# 2025_11_15_drone.net
KiCad netlist of a schematic drawn in EasyEDA Pro
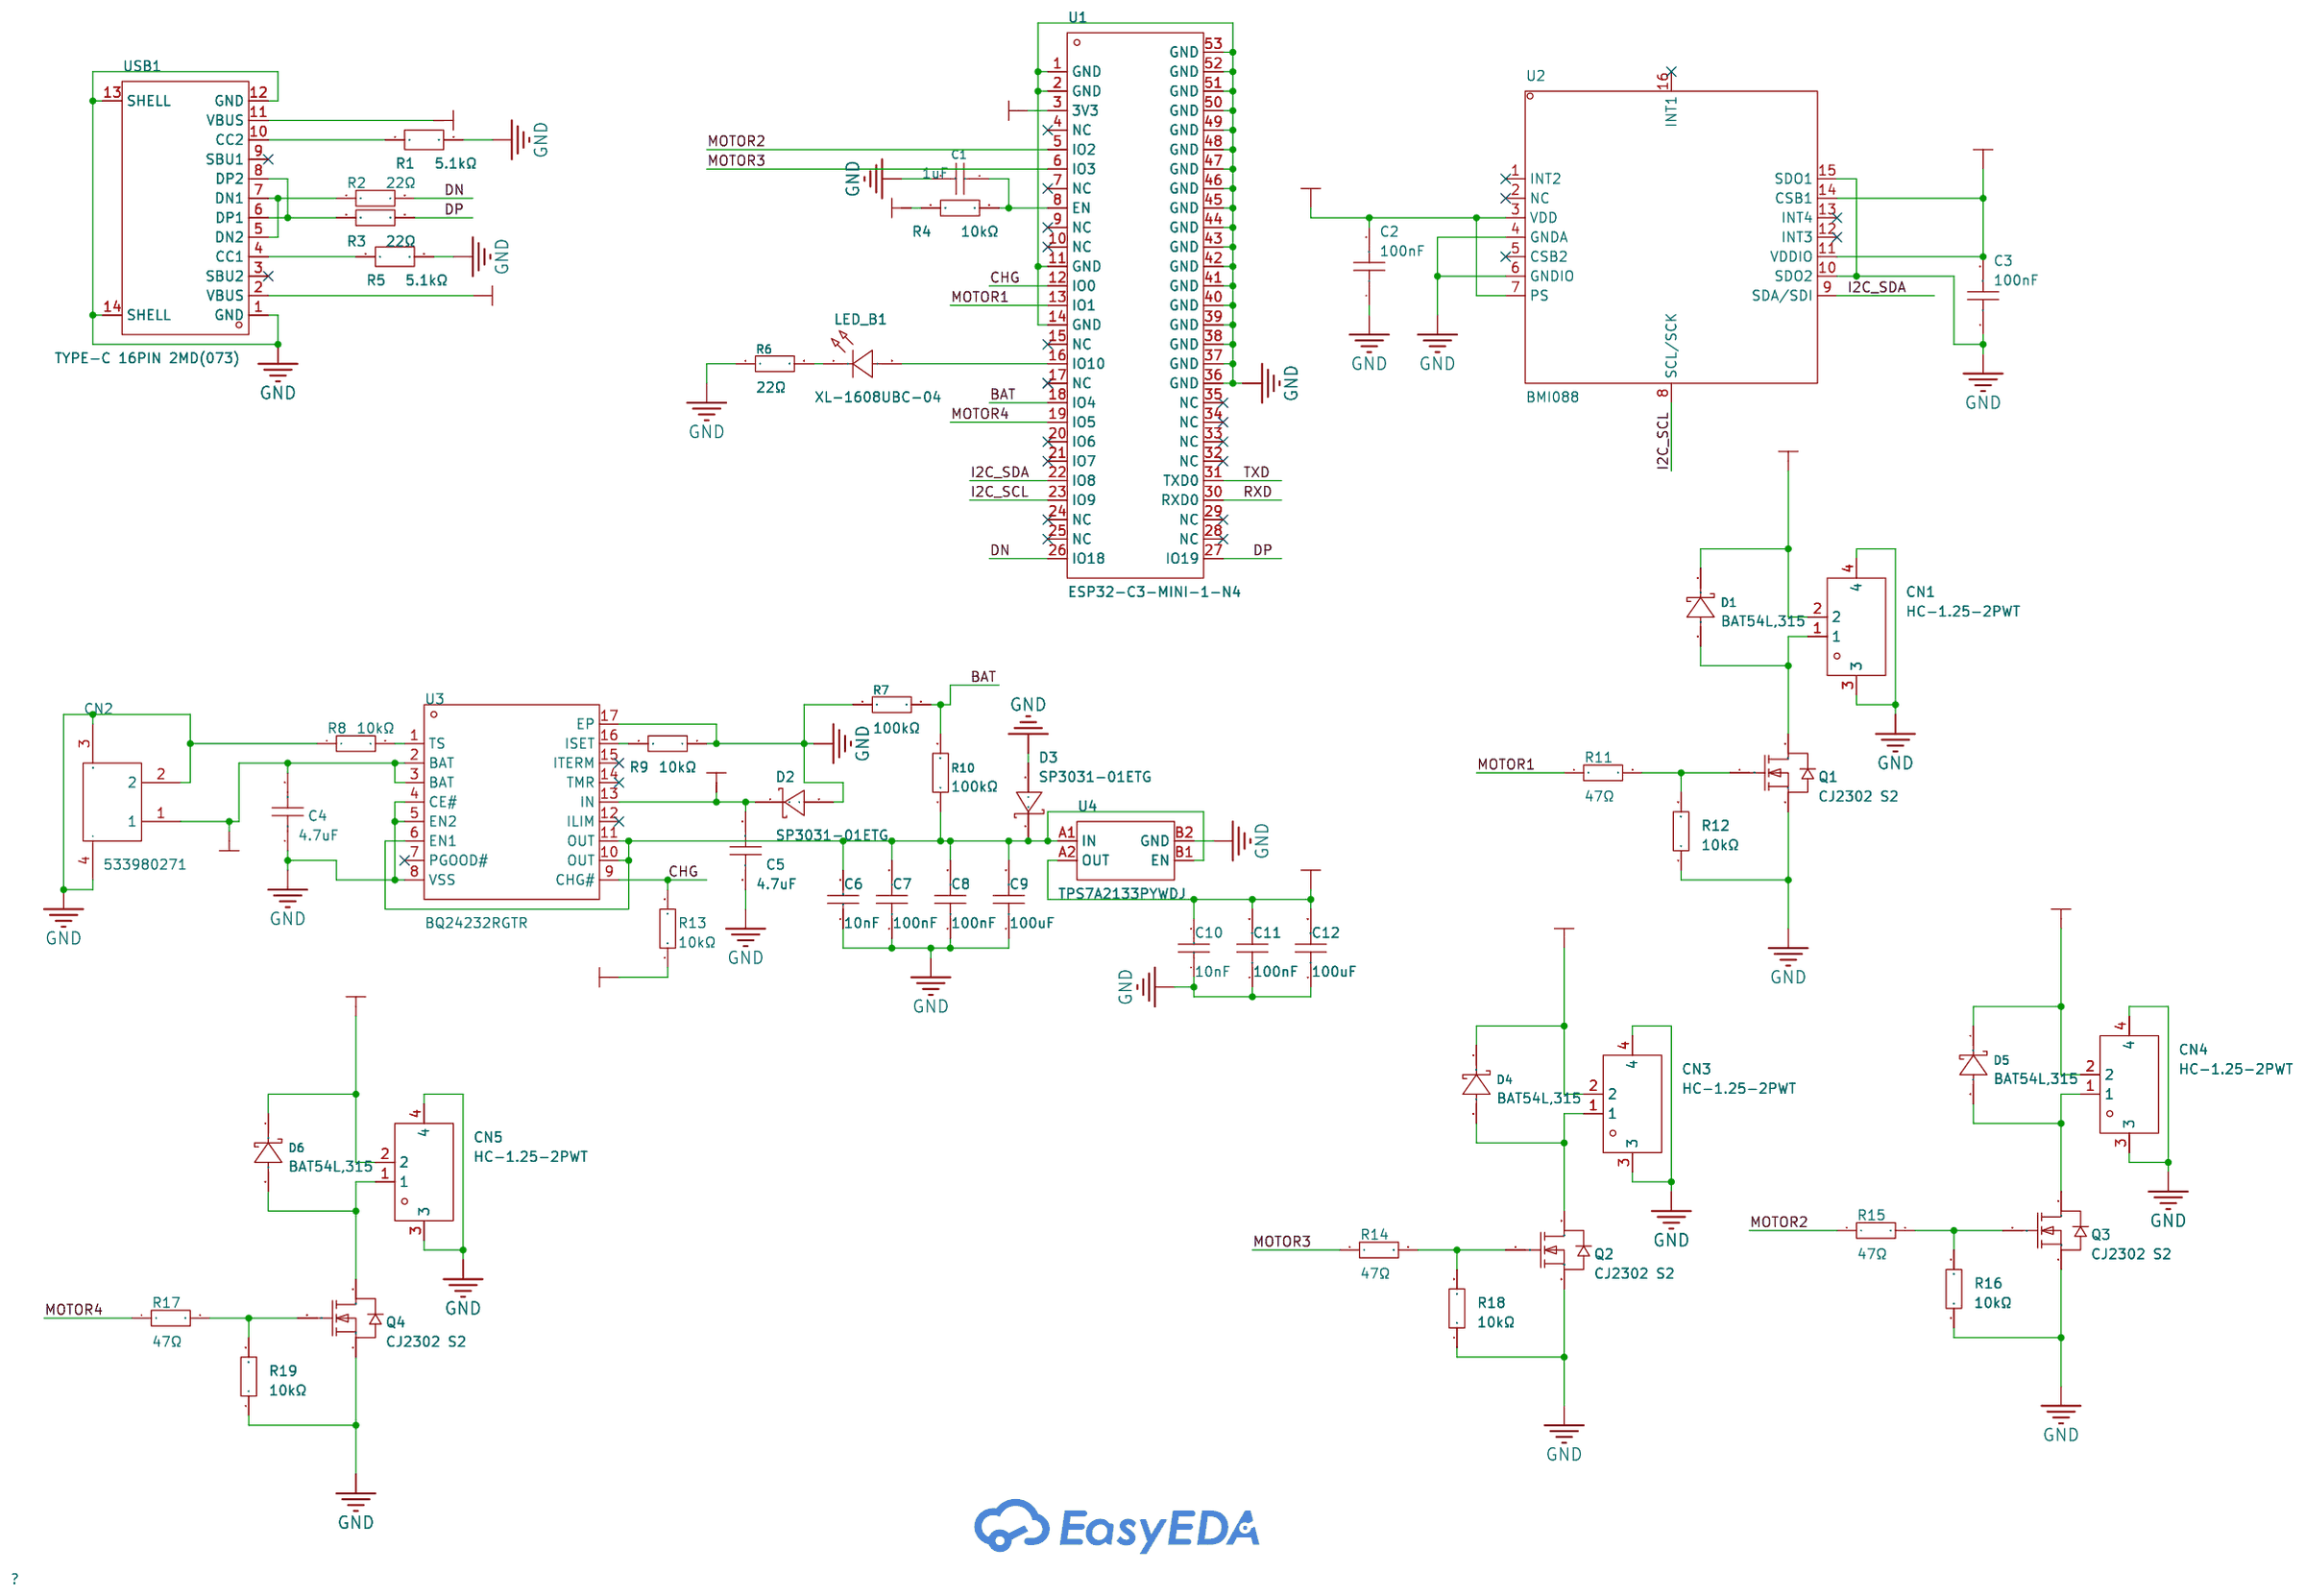
[diagram p0: schematic sheet]

(export (version "E")
  (design (tool "Eeschema 10.0.6"))
  (components
    (comp (ref "C1")
      (value "1uF")
      (footprint "easyedapro:C0402")
      (description "Capacitance:1uF Tolerance:±10% Tolerance:±10% Voltage Rating:16V Temperature Coefficient:X5R")
      (fields
        (field (name "Manufacturer Part") "CL05A105KO5NNNC")
        (field (name "Manufacturer") "SAMSUNG(三星)")
      )
      (libsource (lib "easyedapro") (part "CL05A105KO5NNNC"))
    )
    (comp (ref "C2")
      (value "100nF")
      (footprint "easyedapro:C0402")
      (fields
        (field (name "Manufacturer Part") "CL05B104KO5NNNC")
        (field (name "Manufacturer") "SAMSUNG(三星)")
      )
      (libsource (lib "easyedapro") (part "CL05B104KO5NNNC"))
    )
    (comp (ref "C3")
      (value "100nF")
      (footprint "easyedapro:C0402")
      (fields
        (field (name "Manufacturer Part") "CL05B104KO5NNNC")
        (field (name "Manufacturer") "SAMSUNG(三星)")
      )
      (libsource (lib "easyedapro") (part "CL05B104KO5NNNC"))
    )
    (comp (ref "C4")
      (value "4.7uF")
      (footprint "easyedapro:C0402")
      (description "Capacitance:4.7uF Tolerance:±20% Tolerance:±20% Voltage Rating:6.3V Temperature Coefficient:X5R")
      (fields
        (field (name "Manufacturer Part") "CL05A475MQ5NRNC")
        (field (name "Manufacturer") "SAMSUNG(三星)")
      )
      (libsource (lib "easyedapro") (part "CL05A475MQ5NRNC_C307423"))
    )
    (comp (ref "C5")
      (value "4.7uF")
      (footprint "easyedapro:C0402")
      (description "Capacitance:4.7uF Tolerance:±20% Tolerance:±20% Voltage Rating:6.3V Temperature Coefficient:X5R")
      (fields
        (field (name "Manufacturer Part") "CL05A475MQ5NRNC")
        (field (name "Manufacturer") "SAMSUNG(三星)")
      )
      (libsource (lib "easyedapro") (part "CL05A475MQ5NRNC_C307423"))
    )
    (comp (ref "C6")
      (value "10nF")
      (footprint "easyedapro:C0402")
      (description "Capacitance:10nF Tolerance:±10% Tolerance:±10% Voltage Rating:50V Temperature Coefficient:X7R")
      (fields
        (field (name "Manufacturer Part") "CL05B103KB5NNNC")
        (field (name "Manufacturer") "SAMSUNG(三星)")
      )
      (libsource (lib "easyedapro") (part "CL05B103KB5NNNC"))
    )
    (comp (ref "C7")
      (value "100nF")
      (footprint "easyedapro:C0603")
      (description "Capacitance:100nF Tolerance:±10% Tolerance:±10% Voltage Rating:50V Temperature Coefficient:X7R")
      (fields
        (field (name "Manufacturer Part") "CC0603KRX7R9BB104")
        (field (name "Manufacturer") "YAGEO(国巨)")
      )
      (libsource (lib "easyedapro") (part "CC0603KRX7R9BB104"))
    )
    (comp (ref "C8")
      (value "100nF")
      (footprint "easyedapro:C0603")
      (description "Capacitance:100nF Tolerance:±10% Tolerance:±10% Voltage Rating:50V Temperature Coefficient:X7R")
      (fields
        (field (name "Manufacturer Part") "CC0603KRX7R9BB104")
        (field (name "Manufacturer") "YAGEO(国巨)")
      )
      (libsource (lib "easyedapro") (part "CC0603KRX7R9BB104"))
    )
    (comp (ref "C9")
      (value "100uF")
      (footprint "easyedapro:C1206")
      (description "Capacitance:100uF Tolerance:±20% Tolerance:±20% Voltage Rating:10V Temperature Coefficient:X5R")
      (fields
        (field (name "Manufacturer Part") "HGC1206R5107M100NSPJ")
        (field (name "Manufacturer") "Chinocera(华瓷)")
      )
      (libsource (lib "easyedapro") (part "HGC1206R5107M100NSPJ"))
    )
    (comp (ref "C10")
      (value "10nF")
      (footprint "easyedapro:C0402")
      (description "Capacitance:10nF Tolerance:±10% Tolerance:±10% Voltage Rating:50V Temperature Coefficient:X7R")
      (fields
        (field (name "Manufacturer Part") "CL05B103KB5NNNC")
        (field (name "Manufacturer") "SAMSUNG(三星)")
      )
      (libsource (lib "easyedapro") (part "CL05B103KB5NNNC"))
    )
    (comp (ref "C11")
      (value "100nF")
      (footprint "easyedapro:C0603")
      (description "Capacitance:100nF Tolerance:±10% Tolerance:±10% Voltage Rating:50V Temperature Coefficient:X7R")
      (fields
        (field (name "Manufacturer Part") "CC0603KRX7R9BB104")
        (field (name "Manufacturer") "YAGEO(国巨)")
      )
      (libsource (lib "easyedapro") (part "CC0603KRX7R9BB104"))
    )
    (comp (ref "C12")
      (value "100uF")
      (footprint "easyedapro:C1206")
      (description "Capacitance:100uF Tolerance:±20% Tolerance:±20% Voltage Rating:10V Temperature Coefficient:X5R")
      (fields
        (field (name "Manufacturer Part") "HGC1206R5107M100NSPJ")
        (field (name "Manufacturer") "Chinocera(华瓷)")
      )
      (libsource (lib "easyedapro") (part "HGC1206R5107M100NSPJ"))
    )
    (comp (ref "CN1")
      (value "HC-1.25-2PWT")
      (footprint "easyedapro:CONN-SMD_2P-P1.25-HC-1.25-2PWT")
      (fields (field (name "Manufacturer") "HCTL(华灿天禄)"))
      (libsource (lib "easyedapro") (part "HC-1.25-2PWT"))
    )
    (comp (ref "CN2")
      (value "533980271")
      (footprint "easyedapro:CONN-SMD_2P-P1.25_053398-0X71")
      (fields (field (name "Manufacturer") "MOLEX"))
      (libsource (lib "easyedapro") (part "0533980271"))
    )
    (comp (ref "CN3")
      (value "HC-1.25-2PWT")
      (footprint "easyedapro:CONN-SMD_2P-P1.25-HC-1.25-2PWT")
      (fields (field (name "Manufacturer") "HCTL(华灿天禄)"))
      (libsource (lib "easyedapro") (part "HC-1.25-2PWT"))
    )
    (comp (ref "CN4")
      (value "HC-1.25-2PWT")
      (footprint "easyedapro:CONN-SMD_2P-P1.25-HC-1.25-2PWT")
      (fields (field (name "Manufacturer") "HCTL(华灿天禄)"))
      (libsource (lib "easyedapro") (part "HC-1.25-2PWT"))
    )
    (comp (ref "CN5")
      (value "HC-1.25-2PWT")
      (footprint "easyedapro:CONN-SMD_2P-P1.25-HC-1.25-2PWT")
      (fields (field (name "Manufacturer") "HCTL(华灿天禄)"))
      (libsource (lib "easyedapro") (part "HC-1.25-2PWT"))
    )
    (comp (ref "D1")
      (value "BAT54L,315")
      (footprint "easyedapro:DFN1006-2L-RD")
      (fields (field (name "Manufacturer") "Nexperia(安世)"))
      (libsource (lib "easyedapro") (part "BAT54L,315"))
    )
    (comp (ref "D2")
      (value "SP3031-01ETG")
      (footprint "easyedapro:SOD-882_L1.0-W0.6-RD")
      (fields (field (name "Manufacturer") "Littelfuse(美国力特)"))
      (libsource (lib "easyedapro") (part "SP3031-01ETG"))
    )
    (comp (ref "D3")
      (value "SP3031-01ETG")
      (footprint "easyedapro:SOD-882_L1.0-W0.6-RD")
      (fields (field (name "Manufacturer") "Littelfuse(美国力特)"))
      (libsource (lib "easyedapro") (part "SP3031-01ETG"))
    )
    (comp (ref "D4")
      (value "BAT54L,315")
      (footprint "easyedapro:DFN1006-2L-RD")
      (fields (field (name "Manufacturer") "Nexperia(安世)"))
      (libsource (lib "easyedapro") (part "BAT54L,315"))
    )
    (comp (ref "D5")
      (value "BAT54L,315")
      (footprint "easyedapro:DFN1006-2L-RD")
      (fields (field (name "Manufacturer") "Nexperia(安世)"))
      (libsource (lib "easyedapro") (part "BAT54L,315"))
    )
    (comp (ref "D6")
      (value "BAT54L,315")
      (footprint "easyedapro:DFN1006-2L-RD")
      (fields (field (name "Manufacturer") "Nexperia(安世)"))
      (libsource (lib "easyedapro") (part "BAT54L,315"))
    )
    (comp (ref "LED_B1")
      (value "XL-1608UBC-04")
      (footprint "easyedapro:LED0603-RD_BLUE")
      (fields (field (name "Manufacturer") "XINGLIGHT(成兴光)"))
      (libsource (lib "easyedapro") (part "XL-1608UBC-04"))
    )
    (comp (ref "Q1")
      (value "CJ2302 S2")
      (footprint "easyedapro:SOT-23-3_L3.0-W1.7-P0.95-LS2.9-BR")
      (fields (field (name "Manufacturer") "CJ(江苏长电/长晶)"))
      (libsource (lib "easyedapro") (part "CJ2302 S2"))
    )
    (comp (ref "Q2")
      (value "CJ2302 S2")
      (footprint "easyedapro:SOT-23-3_L3.0-W1.7-P0.95-LS2.9-BR")
      (fields (field (name "Manufacturer") "CJ(江苏长电/长晶)"))
      (libsource (lib "easyedapro") (part "CJ2302 S2"))
    )
    (comp (ref "Q3")
      (value "CJ2302 S2")
      (footprint "easyedapro:SOT-23-3_L3.0-W1.7-P0.95-LS2.9-BR")
      (fields (field (name "Manufacturer") "CJ(江苏长电/长晶)"))
      (libsource (lib "easyedapro") (part "CJ2302 S2"))
    )
    (comp (ref "Q4")
      (value "CJ2302 S2")
      (footprint "easyedapro:SOT-23-3_L3.0-W1.7-P0.95-LS2.9-BR")
      (fields (field (name "Manufacturer") "CJ(江苏长电/长晶)"))
      (libsource (lib "easyedapro") (part "CJ2302 S2"))
    )
    (comp (ref "R1")
      (value "5.1kΩ")
      (footprint "easyedapro:R0603")
      (fields (field (name "Manufacturer Part") "FRC0603F5101TS") (field (name "Manufacturer") "FOJAN(富捷)"))
      (libsource (lib "easyedapro") (part "FRC0603F5101TS"))
    )
    (comp (ref "R2")
      (value "22Ω")
      (footprint "easyedapro:R0603")
      (fields
        (field (name "Manufacturer Part") "0603WAF220JT5E")
        (field (name "Manufacturer") "UNI-ROYAL(厚声)")
      )
      (libsource (lib "easyedapro") (part "0603WAF220JT5E"))
    )
    (comp (ref "R3")
      (value "22Ω")
      (footprint "easyedapro:R0603")
      (fields
        (field (name "Manufacturer Part") "0603WAF220JT5E")
        (field (name "Manufacturer") "UNI-ROYAL(厚声)")
      )
      (libsource (lib "easyedapro") (part "0603WAF220JT5E"))
    )
    (comp (ref "R4")
      (value "10kΩ")
      (footprint "easyedapro:R0603")
      (fields (field (name "Manufacturer Part") "RC0603FR-0710KL") (field (name "Manufacturer") "YAGEO(国巨)"))
      (libsource (lib "easyedapro") (part "RC0603FR-0710KL"))
    )
    (comp (ref "R5")
      (value "5.1kΩ")
      (footprint "easyedapro:R0603")
      (fields (field (name "Manufacturer Part") "FRC0603F5101TS") (field (name "Manufacturer") "FOJAN(富捷)"))
      (libsource (lib "easyedapro") (part "FRC0603F5101TS"))
    )
    (comp (ref "R6")
      (value "22Ω")
      (footprint "easyedapro:R0402")
      (fields
        (field (name "Manufacturer Part") "0402WGF220JTCE")
        (field (name "Manufacturer") "UNI-ROYAL(厚声)")
      )
      (libsource (lib "easyedapro") (part "0402WGF220JTCE"))
    )
    (comp (ref "R7")
      (value "100kΩ")
      (footprint "easyedapro:R0603")
      (fields (field (name "Manufacturer Part") "RC0603FR-07100KL") (field (name "Manufacturer") "YAGEO(国巨)"))
      (libsource (lib "easyedapro") (part "RC0603FR-07100KL"))
    )
    (comp (ref "R8")
      (value "10kΩ")
      (footprint "easyedapro:R0603")
      (fields (field (name "Manufacturer Part") "RC0603FR-0710KL") (field (name "Manufacturer") "YAGEO(国巨)"))
      (libsource (lib "easyedapro") (part "RC0603FR-0710KL"))
    )
    (comp (ref "R9")
      (value "10kΩ")
      (footprint "easyedapro:R0603")
      (fields (field (name "Manufacturer Part") "RC0603FR-0710KL") (field (name "Manufacturer") "YAGEO(国巨)"))
      (libsource (lib "easyedapro") (part "RC0603FR-0710KL"))
    )
    (comp (ref "R10")
      (value "100kΩ")
      (footprint "easyedapro:R0603")
      (fields (field (name "Manufacturer Part") "RC0603FR-07100KL") (field (name "Manufacturer") "YAGEO(国巨)"))
      (libsource (lib "easyedapro") (part "RC0603FR-07100KL"))
    )
    (comp (ref "R11")
      (value "47Ω")
      (footprint "easyedapro:R0402")
      (fields (field (name "Manufacturer Part") "RC0402FR-0747RL") (field (name "Manufacturer") "YAGEO(国巨)"))
      (libsource (lib "easyedapro") (part "RC0402FR-0747RL"))
    )
    (comp (ref "R12")
      (value "10kΩ")
      (footprint "easyedapro:R0402")
      (fields (field (name "Manufacturer Part") "RC0402FR-0710KL") (field (name "Manufacturer") "YAGEO(国巨)"))
      (libsource (lib "easyedapro") (part "RC0402FR-0710KL"))
    )
    (comp (ref "R13")
      (value "10kΩ")
      (footprint "easyedapro:R0603")
      (fields (field (name "Manufacturer Part") "RC0603FR-0710KL") (field (name "Manufacturer") "YAGEO(国巨)"))
      (libsource (lib "easyedapro") (part "RC0603FR-0710KL"))
    )
    (comp (ref "R14")
      (value "47Ω")
      (footprint "easyedapro:R0402")
      (fields (field (name "Manufacturer Part") "RC0402FR-0747RL") (field (name "Manufacturer") "YAGEO(国巨)"))
      (libsource (lib "easyedapro") (part "RC0402FR-0747RL"))
    )
    (comp (ref "R15")
      (value "47Ω")
      (footprint "easyedapro:R0402")
      (fields (field (name "Manufacturer Part") "RC0402FR-0747RL") (field (name "Manufacturer") "YAGEO(国巨)"))
      (libsource (lib "easyedapro") (part "RC0402FR-0747RL"))
    )
    (comp (ref "R16")
      (value "10kΩ")
      (footprint "easyedapro:R0402")
      (fields (field (name "Manufacturer Part") "RC0402FR-0710KL") (field (name "Manufacturer") "YAGEO(国巨)"))
      (libsource (lib "easyedapro") (part "RC0402FR-0710KL"))
    )
    (comp (ref "R17")
      (value "47Ω")
      (footprint "easyedapro:R0402")
      (fields (field (name "Manufacturer Part") "RC0402FR-0747RL") (field (name "Manufacturer") "YAGEO(国巨)"))
      (libsource (lib "easyedapro") (part "RC0402FR-0747RL"))
    )
    (comp (ref "R18")
      (value "10kΩ")
      (footprint "easyedapro:R0402")
      (fields (field (name "Manufacturer Part") "RC0402FR-0710KL") (field (name "Manufacturer") "YAGEO(国巨)"))
      (libsource (lib "easyedapro") (part "RC0402FR-0710KL"))
    )
    (comp (ref "R19")
      (value "10kΩ")
      (footprint "easyedapro:R0402")
      (fields (field (name "Manufacturer Part") "RC0402FR-0710KL") (field (name "Manufacturer") "YAGEO(国巨)"))
      (libsource (lib "easyedapro") (part "RC0402FR-0710KL"))
    )
    (comp (ref "U1")
      (value "ESP32-C3-MINI-1-N4")
      (footprint "easyedapro:WIFIM-SMD_ESP32-C3-MINI-1")
      (fields (field (name "Manufacturer") "ESPRESSIF(乐鑫)"))
      (libsource (lib "easyedapro") (part "ESP32-C3-MINI-1-N4"))
    )
    (comp (ref "U2")
      (value "BMI088")
      (footprint "easyedapro:LGA-16_L4.5-W3.0-P0.50-BL")
      (description "Sensor Type:加速度计陀螺仪 Operating Temperature:-40°C~+85°C Operating Temperature:-40°C~+85°C")
      (fields (field (name "Manufacturer") "Bosch(博世)"))
      (libsource (lib "easyedapro") (part "BMI088"))
    )
    (comp (ref "U3")
      (value "BQ24232RGTR")
      (footprint "easyedapro:VQFN-16_L3.0-W3.0-P0.50-TL-EP")
      (fields (field (name "Manufacturer") "TI(德州仪器)"))
      (libsource (lib "easyedapro") (part "BQ24232RGTR"))
    )
    (comp (ref "U4")
      (value "TPS7A2133PYWDJ")
      (footprint "easyedapro:DSBGA-4_L0.6-W0.6-P0.35-TL")
      (fields (field (name "Manufacturer") "TI(德州仪器)"))
      (libsource (lib "easyedapro") (part "TPS7A2133PYWDJ"))
    )
    (comp (ref "USB1")
      (value "TYPE-C 16PIN 2MD(073)")
      (footprint "easyedapro:USB-C-SMD_TYPE-C-6PIN-2MD-073")
      (fields (field (name "Manufacturer") "SHOU HAN(首韩)"))
      (libsource (lib "easyedapro") (part "TYPE-C 16PIN 2MD(073)"))
    )
  )
  (nets
    (net (code "1") (name "/BAT") (class "Default")
      (node (ref "R10") (pin "2") (pinfunction "2_2") (pintype "input"))
      (node (ref "R7") (pin "1") (pinfunction "1_1") (pintype "input"))
      (node (ref "U1") (pin "18") (pinfunction "IO4_18") (pintype "unspecified"))
    )
    (net (code "2") (name "/CHG") (class "Default")
      (node (ref "R13") (pin "2") (pinfunction "2_2") (pintype "input"))
      (node (ref "U1") (pin "12") (pinfunction "IO0_12") (pintype "unspecified"))
      (node (ref "U3") (pin "9") (pinfunction "CHG#_9") (pintype "unspecified"))
    )
    (net (code "3") (name "/DN") (class "Default")
      (node (ref "R2") (pin "2") (pinfunction "2_2") (pintype "input"))
      (node (ref "U1") (pin "26") (pinfunction "IO18_26") (pintype "unspecified"))
    )
    (net (code "4") (name "/DP") (class "Default")
      (node (ref "R3") (pin "2") (pinfunction "2_2") (pintype "input"))
      (node (ref "U1") (pin "27") (pinfunction "IO19_27") (pintype "unspecified"))
    )
    (net (code "5") (name "/I2C_SCL") (class "Default")
      (node (ref "U1") (pin "23") (pinfunction "IO9_23") (pintype "unspecified"))
      (node (ref "U2") (pin "8") (pinfunction "SCL/SCK_8") (pintype "input"))
    )
    (net (code "6") (name "/I2C_SDA") (class "Default")
      (node (ref "U1") (pin "22") (pinfunction "IO8_22") (pintype "unspecified"))
      (node (ref "U2") (pin "9") (pinfunction "SDA/SDI_9") (pintype "input"))
    )
    (net (code "7") (name "/MOTOR1") (class "Default")
      (node (ref "R11") (pin "1") (pinfunction "1_1") (pintype "input"))
      (node (ref "U1") (pin "13") (pinfunction "IO1_13") (pintype "unspecified"))
    )
    (net (code "8") (name "/MOTOR2") (class "Default")
      (node (ref "R15") (pin "1") (pinfunction "1_1") (pintype "input"))
      (node (ref "U1") (pin "5") (pinfunction "IO2_5") (pintype "unspecified"))
    )
    (net (code "9") (name "/MOTOR3") (class "Default")
      (node (ref "R14") (pin "1") (pinfunction "1_1") (pintype "input"))
      (node (ref "U1") (pin "6") (pinfunction "IO3_6") (pintype "unspecified"))
    )
    (net (code "10") (name "/MOTOR4") (class "Default")
      (node (ref "R17") (pin "1") (pinfunction "1_1") (pintype "input"))
      (node (ref "U1") (pin "19") (pinfunction "IO5_19") (pintype "unspecified"))
    )
    (net (code "11") (name "/RXD") (class "Default")
      (node (ref "U1") (pin "30") (pinfunction "RXD0_30") (pintype "unspecified"))
    )
    (net (code "12") (name "/TXD") (class "Default")
      (node (ref "U1") (pin "31") (pinfunction "TXD0_31") (pintype "unspecified"))
    )
    (net (code "13") (name "3V3") (class "Default")
      (node (ref "C10") (pin "2") (pinfunction "2_2") (pintype "input"))
      (node (ref "C11") (pin "2") (pinfunction "2_2") (pintype "unspecified"))
      (node (ref "C12") (pin "2") (pinfunction "2_2") (pintype "unspecified"))
      (node (ref "C2") (pin "2") (pinfunction "2_2") (pintype "unspecified"))
      (node (ref "C3") (pin "2") (pinfunction "2_2") (pintype "unspecified"))
      (node (ref "CN1") (pin "2") (pinfunction "2_2") (pintype "unspecified"))
      (node (ref "CN3") (pin "2") (pinfunction "2_2") (pintype "unspecified"))
      (node (ref "CN4") (pin "2") (pinfunction "2_2") (pintype "unspecified"))
      (node (ref "CN5") (pin "2") (pinfunction "2_2") (pintype "unspecified"))
      (node (ref "D1") (pin "1") (pinfunction "K_1") (pintype "input"))
      (node (ref "D4") (pin "1") (pinfunction "K_1") (pintype "input"))
      (node (ref "D5") (pin "1") (pinfunction "K_1") (pintype "input"))
      (node (ref "D6") (pin "1") (pinfunction "K_1") (pintype "input"))
      (node (ref "R13") (pin "1") (pinfunction "1_1") (pintype "input"))
      (node (ref "R4") (pin "2") (pinfunction "2_2") (pintype "input"))
      (node (ref "U1") (pin "3") (pinfunction "3V3_3") (pintype "unspecified"))
      (node (ref "U2") (pin "11") (pinfunction "VDDIO_11") (pintype "input"))
      (node (ref "U2") (pin "14") (pinfunction "CSB1_14") (pintype "input"))
      (node (ref "U2") (pin "3") (pinfunction "VDD_3") (pintype "input"))
      (node (ref "U2") (pin "7") (pinfunction "PS_7") (pintype "input"))
      (node (ref "U4") (pin "A2") (pinfunction "OUT_A2") (pintype "unspecified"))
    )
    (net (code "14") (name "GND") (class "Default")
      (node (ref "C1") (pin "2") (pinfunction "2_2") (pintype "input"))
      (node (ref "C10") (pin "1") (pinfunction "1_1") (pintype "input"))
      (node (ref "C11") (pin "1") (pinfunction "1_1") (pintype "unspecified"))
      (node (ref "C12") (pin "1") (pinfunction "1_1") (pintype "unspecified"))
      (node (ref "C2") (pin "1") (pinfunction "1_1") (pintype "unspecified"))
      (node (ref "C3") (pin "1") (pinfunction "1_1") (pintype "unspecified"))
      (node (ref "C4") (pin "1") (pinfunction "1_1") (pintype "unspecified"))
      (node (ref "C5") (pin "1") (pinfunction "1_1") (pintype "unspecified"))
      (node (ref "C6") (pin "1") (pinfunction "1_1") (pintype "input"))
      (node (ref "C7") (pin "1") (pinfunction "1_1") (pintype "unspecified"))
      (node (ref "C8") (pin "1") (pinfunction "1_1") (pintype "unspecified"))
      (node (ref "C9") (pin "1") (pinfunction "1_1") (pintype "unspecified"))
      (node (ref "CN1") (pin "3") (pinfunction "3_3") (pintype "unspecified"))
      (node (ref "CN1") (pin "4") (pinfunction "4_4") (pintype "unspecified"))
      (node (ref "CN2") (pin "2") (pinfunction "2_2") (pintype "unspecified"))
      (node (ref "CN2") (pin "3") (pinfunction "3_3") (pintype "unspecified"))
      (node (ref "CN2") (pin "4") (pinfunction "4_4") (pintype "unspecified"))
      (node (ref "CN3") (pin "3") (pinfunction "3_3") (pintype "unspecified"))
      (node (ref "CN3") (pin "4") (pinfunction "4_4") (pintype "unspecified"))
      (node (ref "CN4") (pin "3") (pinfunction "3_3") (pintype "unspecified"))
      (node (ref "CN4") (pin "4") (pinfunction "4_4") (pintype "unspecified"))
      (node (ref "CN5") (pin "3") (pinfunction "3_3") (pintype "unspecified"))
      (node (ref "CN5") (pin "4") (pinfunction "4_4") (pintype "unspecified"))
      (node (ref "D2") (pin "2") (pinfunction "A_2") (pintype "unspecified"))
      (node (ref "D3") (pin "2") (pinfunction "A_2") (pintype "unspecified"))
      (node (ref "Q1") (pin "2") (pinfunction "S_2") (pintype "unspecified"))
      (node (ref "Q2") (pin "2") (pinfunction "S_2") (pintype "unspecified"))
      (node (ref "Q3") (pin "2") (pinfunction "S_2") (pintype "unspecified"))
      (node (ref "Q4") (pin "2") (pinfunction "S_2") (pintype "unspecified"))
      (node (ref "R1") (pin "2") (pinfunction "2_2") (pintype "unspecified"))
      (node (ref "R12") (pin "1") (pinfunction "1_1") (pintype "input"))
      (node (ref "R16") (pin "1") (pinfunction "1_1") (pintype "input"))
      (node (ref "R18") (pin "1") (pinfunction "1_1") (pintype "input"))
      (node (ref "R19") (pin "1") (pinfunction "1_1") (pintype "input"))
      (node (ref "R5") (pin "2") (pinfunction "2_2") (pintype "unspecified"))
      (node (ref "R6") (pin "1") (pinfunction "1_1") (pintype "input"))
      (node (ref "R7") (pin "2") (pinfunction "2_2") (pintype "input"))
      (node (ref "R8") (pin "1") (pinfunction "1_1") (pintype "input"))
      (node (ref "R9") (pin "1") (pinfunction "1_1") (pintype "input"))
      (node (ref "U1") (pin "1") (pinfunction "GND_1") (pintype "unspecified"))
      (node (ref "U1") (pin "11") (pinfunction "GND_11") (pintype "unspecified"))
      (node (ref "U1") (pin "14") (pinfunction "GND_14") (pintype "unspecified"))
      (node (ref "U1") (pin "2") (pinfunction "GND_2") (pintype "unspecified"))
      (node (ref "U1") (pin "36") (pinfunction "GND_36") (pintype "unspecified"))
      (node (ref "U1") (pin "37") (pinfunction "GND_37") (pintype "unspecified"))
      (node (ref "U1") (pin "38") (pinfunction "GND_38") (pintype "unspecified"))
      (node (ref "U1") (pin "39") (pinfunction "GND_39") (pintype "unspecified"))
      (node (ref "U1") (pin "40") (pinfunction "GND_40") (pintype "unspecified"))
      (node (ref "U1") (pin "41") (pinfunction "GND_41") (pintype "unspecified"))
      (node (ref "U1") (pin "42") (pinfunction "GND_42") (pintype "unspecified"))
      (node (ref "U1") (pin "43") (pinfunction "GND_43") (pintype "unspecified"))
      (node (ref "U1") (pin "44") (pinfunction "GND_44") (pintype "unspecified"))
      (node (ref "U1") (pin "45") (pinfunction "GND_45") (pintype "unspecified"))
      (node (ref "U1") (pin "46") (pinfunction "GND_46") (pintype "unspecified"))
      (node (ref "U1") (pin "47") (pinfunction "GND_47") (pintype "unspecified"))
      (node (ref "U1") (pin "48") (pinfunction "GND_48") (pintype "unspecified"))
      (node (ref "U1") (pin "49") (pinfunction "GND_49") (pintype "unspecified"))
      (node (ref "U1") (pin "50") (pinfunction "GND_50") (pintype "unspecified"))
      (node (ref "U1") (pin "51") (pinfunction "GND_51") (pintype "unspecified"))
      (node (ref "U1") (pin "52") (pinfunction "GND_52") (pintype "unspecified"))
      (node (ref "U1") (pin "53") (pinfunction "GND_53") (pintype "unspecified"))
      (node (ref "U2") (pin "10") (pinfunction "SDO2_10") (pintype "input"))
      (node (ref "U2") (pin "15") (pinfunction "SDO1_15") (pintype "input"))
      (node (ref "U2") (pin "4") (pinfunction "GNDA_4") (pintype "input"))
      (node (ref "U2") (pin "6") (pinfunction "GNDIO_6") (pintype "input"))
      (node (ref "U3") (pin "17") (pinfunction "EP_17") (pintype "unspecified"))
      (node (ref "U3") (pin "4") (pinfunction "CE#_4") (pintype "unspecified"))
      (node (ref "U3") (pin "5") (pinfunction "EN2_5") (pintype "unspecified"))
      (node (ref "U3") (pin "8") (pinfunction "VSS_8") (pintype "unspecified"))
      (node (ref "U4") (pin "B2") (pinfunction "GND_B2") (pintype "unspecified"))
      (node (ref "USB1") (pin "1") (pinfunction "GND_1") (pintype "unspecified"))
      (node (ref "USB1") (pin "12") (pinfunction "GND_12") (pintype "unspecified"))
      (node (ref "USB1") (pin "13") (pinfunction "SHELL_13") (pintype "unspecified"))
      (node (ref "USB1") (pin "14") (pinfunction "SHELL_14") (pintype "unspecified"))
    )
    (net (code "15") (name "Net-(D1-A)") (class "Default")
      (node (ref "CN1") (pin "1") (pinfunction "1_1") (pintype "unspecified"))
      (node (ref "D1") (pin "2") (pinfunction "A_2") (pintype "input"))
      (node (ref "Q1") (pin "3") (pinfunction "D_3") (pintype "unspecified"))
    )
    (net (code "16") (name "Net-(D3-K)") (class "Default")
      (node (ref "C6") (pin "2") (pinfunction "2_2") (pintype "input"))
      (node (ref "C7") (pin "2") (pinfunction "2_2") (pintype "unspecified"))
      (node (ref "C8") (pin "2") (pinfunction "2_2") (pintype "unspecified"))
      (node (ref "C9") (pin "2") (pinfunction "2_2") (pintype "unspecified"))
      (node (ref "D3") (pin "1") (pinfunction "K_1") (pintype "unspecified"))
      (node (ref "R10") (pin "1") (pinfunction "1_1") (pintype "input"))
      (node (ref "U3") (pin "10") (pinfunction "OUT_10") (pintype "unspecified"))
      (node (ref "U3") (pin "11") (pinfunction "OUT_11") (pintype "unspecified"))
      (node (ref "U3") (pin "6") (pinfunction "EN1_6") (pintype "unspecified"))
      (node (ref "U4") (pin "A1") (pinfunction "IN_A1") (pintype "unspecified"))
      (node (ref "U4") (pin "B1") (pinfunction "EN_B1") (pintype "unspecified"))
    )
    (net (code "17") (name "Net-(D4-A)") (class "Default")
      (node (ref "CN3") (pin "1") (pinfunction "1_1") (pintype "unspecified"))
      (node (ref "D4") (pin "2") (pinfunction "A_2") (pintype "input"))
      (node (ref "Q2") (pin "3") (pinfunction "D_3") (pintype "unspecified"))
    )
    (net (code "18") (name "Net-(D5-A)") (class "Default")
      (node (ref "CN4") (pin "1") (pinfunction "1_1") (pintype "unspecified"))
      (node (ref "D5") (pin "2") (pinfunction "A_2") (pintype "input"))
      (node (ref "Q3") (pin "3") (pinfunction "D_3") (pintype "unspecified"))
    )
    (net (code "19") (name "Net-(D6-A)") (class "Default")
      (node (ref "CN5") (pin "1") (pinfunction "1_1") (pintype "unspecified"))
      (node (ref "D6") (pin "2") (pinfunction "A_2") (pintype "input"))
      (node (ref "Q4") (pin "3") (pinfunction "D_3") (pintype "unspecified"))
    )
    (net (code "20") (name "Net-(LED_B1-A)") (class "Default")
      (node (ref "LED_B1") (pin "2") (pinfunction "A_2") (pintype "unspecified"))
      (node (ref "U1") (pin "16") (pinfunction "IO10_16") (pintype "unspecified"))
    )
    (net (code "21") (name "Net-(LED_B1-K)") (class "Default")
      (node (ref "LED_B1") (pin "1") (pinfunction "K_1") (pintype "unspecified"))
      (node (ref "R6") (pin "2") (pinfunction "2_2") (pintype "input"))
    )
    (net (code "22") (name "Net-(Q1-G)") (class "Default")
      (node (ref "Q1") (pin "1") (pinfunction "G_1") (pintype "unspecified"))
      (node (ref "R11") (pin "2") (pinfunction "2_2") (pintype "input"))
      (node (ref "R12") (pin "2") (pinfunction "2_2") (pintype "input"))
    )
    (net (code "23") (name "Net-(Q2-G)") (class "Default")
      (node (ref "Q2") (pin "1") (pinfunction "G_1") (pintype "unspecified"))
      (node (ref "R14") (pin "2") (pinfunction "2_2") (pintype "input"))
      (node (ref "R18") (pin "2") (pinfunction "2_2") (pintype "input"))
    )
    (net (code "24") (name "Net-(Q3-G)") (class "Default")
      (node (ref "Q3") (pin "1") (pinfunction "G_1") (pintype "unspecified"))
      (node (ref "R15") (pin "2") (pinfunction "2_2") (pintype "input"))
      (node (ref "R16") (pin "2") (pinfunction "2_2") (pintype "input"))
    )
    (net (code "25") (name "Net-(Q4-G)") (class "Default")
      (node (ref "Q4") (pin "1") (pinfunction "G_1") (pintype "unspecified"))
      (node (ref "R17") (pin "2") (pinfunction "2_2") (pintype "input"))
      (node (ref "R19") (pin "2") (pinfunction "2_2") (pintype "input"))
    )
    (net (code "26") (name "Net-(U1-EN)") (class "Default")
      (node (ref "C1") (pin "1") (pinfunction "1_1") (pintype "input"))
      (node (ref "R4") (pin "1") (pinfunction "1_1") (pintype "input"))
      (node (ref "U1") (pin "8") (pinfunction "EN_8") (pintype "unspecified"))
    )
    (net (code "27") (name "Net-(U3-ISET)") (class "Default")
      (node (ref "R9") (pin "2") (pinfunction "2_2") (pintype "input"))
      (node (ref "U3") (pin "16") (pinfunction "ISET_16") (pintype "unspecified"))
    )
    (net (code "28") (name "Net-(U3-TS)") (class "Default")
      (node (ref "R8") (pin "2") (pinfunction "2_2") (pintype "input"))
      (node (ref "U3") (pin "1") (pinfunction "TS_1") (pintype "unspecified"))
    )
    (net (code "29") (name "Net-(USB1-CC1)") (class "Default")
      (node (ref "R5") (pin "1") (pinfunction "1_1") (pintype "unspecified"))
      (node (ref "USB1") (pin "4") (pinfunction "CC1_4") (pintype "unspecified"))
    )
    (net (code "30") (name "Net-(USB1-CC2)") (class "Default")
      (node (ref "R1") (pin "1") (pinfunction "1_1") (pintype "unspecified"))
      (node (ref "USB1") (pin "10") (pinfunction "CC2_10") (pintype "unspecified"))
    )
    (net (code "31") (name "Net-(USB1-DN1)") (class "Default")
      (node (ref "R2") (pin "1") (pinfunction "1_1") (pintype "input"))
      (node (ref "USB1") (pin "5") (pinfunction "DN2_5") (pintype "unspecified"))
      (node (ref "USB1") (pin "7") (pinfunction "DN1_7") (pintype "unspecified"))
    )
    (net (code "32") (name "Net-(USB1-DP1)") (class "Default")
      (node (ref "R3") (pin "1") (pinfunction "1_1") (pintype "input"))
      (node (ref "USB1") (pin "6") (pinfunction "DP1_6") (pintype "unspecified"))
      (node (ref "USB1") (pin "8") (pinfunction "DP2_8") (pintype "unspecified"))
    )
    (net (code "33") (name "VBAT") (class "Default")
      (node (ref "C4") (pin "2") (pinfunction "2_2") (pintype "unspecified"))
      (node (ref "CN2") (pin "1") (pinfunction "1_1") (pintype "unspecified"))
      (node (ref "U3") (pin "2") (pinfunction "BAT_2") (pintype "unspecified"))
      (node (ref "U3") (pin "3") (pinfunction "BAT_3") (pintype "unspecified"))
    )
    (net (code "34") (name "VUSB") (class "Default")
      (node (ref "C5") (pin "2") (pinfunction "2_2") (pintype "unspecified"))
      (node (ref "D2") (pin "1") (pinfunction "K_1") (pintype "unspecified"))
      (node (ref "U3") (pin "13") (pinfunction "IN_13") (pintype "unspecified"))
      (node (ref "USB1") (pin "11") (pinfunction "VBUS_11") (pintype "unspecified"))
      (node (ref "USB1") (pin "2") (pinfunction "VBUS_2") (pintype "unspecified"))
    )
    (net (code "35") (name "unconnected-(U1-IO6-Pad20)") (class "Default")
      (node (ref "U1") (pin "20") (pinfunction "IO6_20") (pintype "unspecified+no_connect"))
    )
    (net (code "36") (name "unconnected-(U1-IO7-Pad21)") (class "Default")
      (node (ref "U1") (pin "21") (pinfunction "IO7_21") (pintype "unspecified+no_connect"))
    )
    (net (code "37") (name "unconnected-(U1-NC-Pad4)") (class "Default")
      (node (ref "U1") (pin "4") (pinfunction "NC_4") (pintype "unspecified+no_connect"))
    )
    (net (code "38") (name "unconnected-(U1-NC-Pad7)") (class "Default")
      (node (ref "U1") (pin "7") (pinfunction "NC_7") (pintype "unspecified+no_connect"))
    )
    (net (code "39") (name "unconnected-(U1-NC-Pad9)") (class "Default")
      (node (ref "U1") (pin "9") (pinfunction "NC_9") (pintype "unspecified+no_connect"))
    )
    (net (code "40") (name "unconnected-(U1-NC-Pad10)") (class "Default")
      (node (ref "U1") (pin "10") (pinfunction "NC_10") (pintype "unspecified+no_connect"))
    )
    (net (code "41") (name "unconnected-(U1-NC-Pad15)") (class "Default")
      (node (ref "U1") (pin "15") (pinfunction "NC_15") (pintype "unspecified+no_connect"))
    )
    (net (code "42") (name "unconnected-(U1-NC-Pad17)") (class "Default")
      (node (ref "U1") (pin "17") (pinfunction "NC_17") (pintype "unspecified+no_connect"))
    )
    (net (code "43") (name "unconnected-(U1-NC-Pad24)") (class "Default")
      (node (ref "U1") (pin "24") (pinfunction "NC_24") (pintype "unspecified+no_connect"))
    )
    (net (code "44") (name "unconnected-(U1-NC-Pad25)") (class "Default")
      (node (ref "U1") (pin "25") (pinfunction "NC_25") (pintype "unspecified+no_connect"))
    )
    (net (code "45") (name "unconnected-(U1-NC-Pad28)") (class "Default")
      (node (ref "U1") (pin "28") (pinfunction "NC_28") (pintype "unspecified+no_connect"))
    )
    (net (code "46") (name "unconnected-(U1-NC-Pad29)") (class "Default")
      (node (ref "U1") (pin "29") (pinfunction "NC_29") (pintype "unspecified+no_connect"))
    )
    (net (code "47") (name "unconnected-(U1-NC-Pad32)") (class "Default")
      (node (ref "U1") (pin "32") (pinfunction "NC_32") (pintype "unspecified+no_connect"))
    )
    (net (code "48") (name "unconnected-(U1-NC-Pad33)") (class "Default")
      (node (ref "U1") (pin "33") (pinfunction "NC_33") (pintype "unspecified+no_connect"))
    )
    (net (code "49") (name "unconnected-(U1-NC-Pad34)") (class "Default")
      (node (ref "U1") (pin "34") (pinfunction "NC_34") (pintype "unspecified+no_connect"))
    )
    (net (code "50") (name "unconnected-(U1-NC-Pad35)") (class "Default")
      (node (ref "U1") (pin "35") (pinfunction "NC_35") (pintype "unspecified+no_connect"))
    )
    (net (code "51") (name "unconnected-(U2-CSB2-Pad5)") (class "Default")
      (node (ref "U2") (pin "5") (pinfunction "CSB2_5") (pintype "input+no_connect"))
    )
    (net (code "52") (name "unconnected-(U2-INT1-Pad16)") (class "Default")
      (node (ref "U2") (pin "16") (pinfunction "INT1_16") (pintype "input+no_connect"))
    )
    (net (code "53") (name "unconnected-(U2-INT2-Pad1)") (class "Default")
      (node (ref "U2") (pin "1") (pinfunction "INT2_1") (pintype "input+no_connect"))
    )
    (net (code "54") (name "unconnected-(U2-INT3-Pad12)") (class "Default")
      (node (ref "U2") (pin "12") (pinfunction "INT3_12") (pintype "input+no_connect"))
    )
    (net (code "55") (name "unconnected-(U2-INT4-Pad13)") (class "Default")
      (node (ref "U2") (pin "13") (pinfunction "INT4_13") (pintype "input+no_connect"))
    )
    (net (code "56") (name "unconnected-(U2-NC-Pad2)") (class "Default")
      (node (ref "U2") (pin "2") (pinfunction "NC_2") (pintype "input+no_connect"))
    )
    (net (code "57") (name "unconnected-(U3-ILIM-Pad12)") (class "Default")
      (node (ref "U3") (pin "12") (pinfunction "ILIM_12") (pintype "unspecified+no_connect"))
    )
    (net (code "58") (name "unconnected-(U3-ITERM-Pad15)") (class "Default")
      (node (ref "U3") (pin "15") (pinfunction "ITERM_15") (pintype "unspecified+no_connect"))
    )
    (net (code "59") (name "unconnected-(U3-PGOOD#-Pad7)") (class "Default")
      (node (ref "U3") (pin "7") (pinfunction "PGOOD#_7") (pintype "unspecified+no_connect"))
    )
    (net (code "60") (name "unconnected-(U3-TMR-Pad14)") (class "Default")
      (node (ref "U3") (pin "14") (pinfunction "TMR_14") (pintype "unspecified+no_connect"))
    )
    (net (code "61") (name "unconnected-(USB1-SBU1-Pad9)") (class "Default")
      (node (ref "USB1") (pin "9") (pinfunction "SBU1_9") (pintype "unspecified+no_connect"))
    )
    (net (code "62") (name "unconnected-(USB1-SBU2-Pad3)") (class "Default")
      (node (ref "USB1") (pin "3") (pinfunction "SBU2_3") (pintype "unspecified+no_connect"))
    )
  )
)
